# Logic.net
KiCad netlist of a schematic drawn in EAGLE
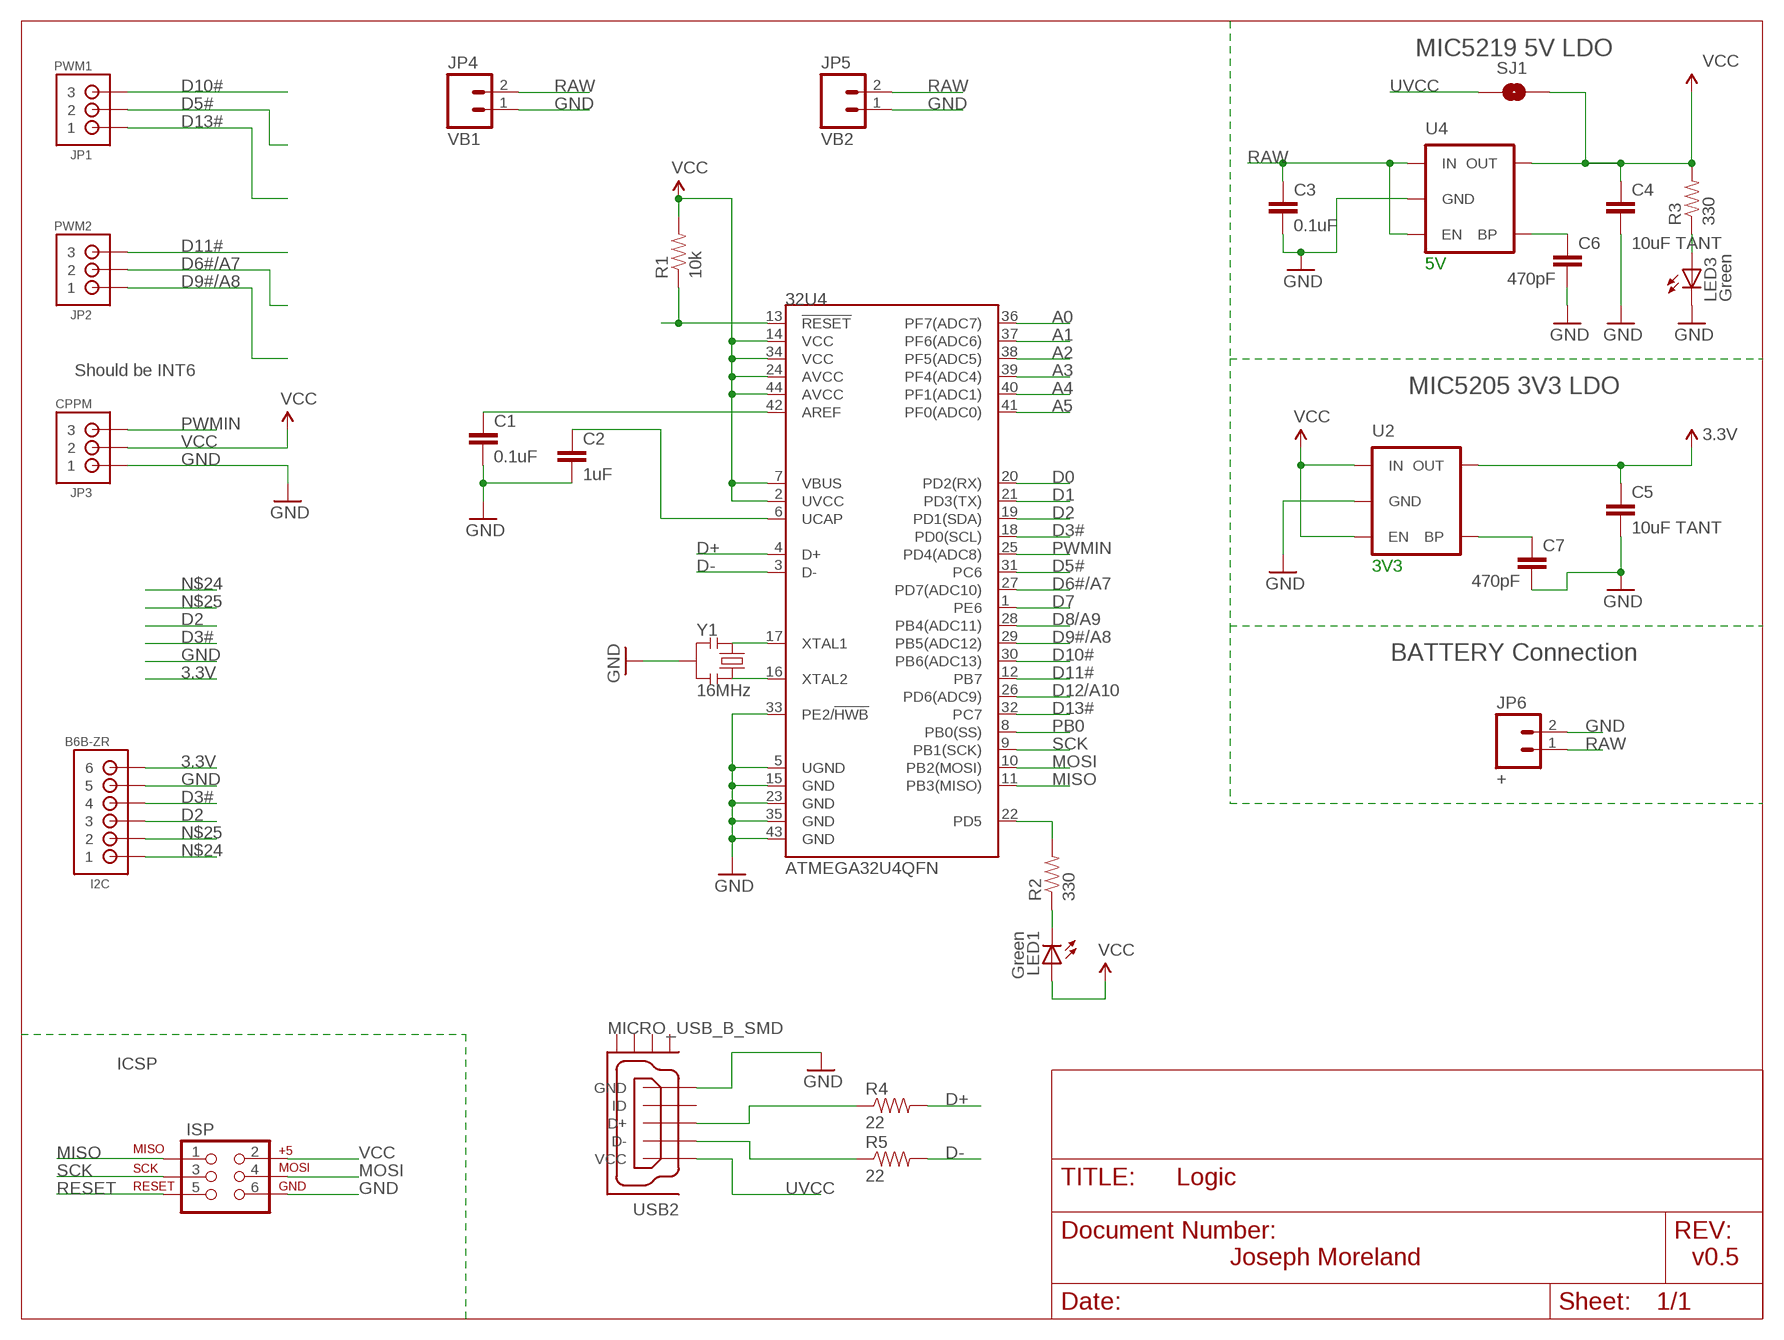
[diagram p0: schematic, sheet 1]

(export (version "E")
  (design (tool "Eeschema 10.0.6"))
  (components
    (comp (ref "32U4")
      (value "ATMEGA32U4QFN")
      (footprint "eagle-import:SPARKFUN-DIGITALIC_QFN-44")
      (fields (field (name "PARTNO") "ATMEGA32U4-MU"))
      (libsource (lib "eagle-import") (part "ATMEGA32U4QFN"))
    )
    (comp (ref "C1")
      (value "0.1uF")
      (footprint "eagle-import:0603-CAP")
      (fields (field (name "PARTNO") "C0603C104K8RACTU"))
      (libsource (lib "eagle-import") (part "CAP0603-CAP"))
    )
    (comp (ref "C2")
      (value "1uF")
      (footprint "eagle-import:0402-CAP")
      (fields (field (name "PARTNO") "LMK105BJ105KV-F"))
      (libsource (lib "eagle-import") (part "CAP0402-CAP"))
    )
    (comp (ref "C3")
      (value "0.1uF")
      (footprint "eagle-import:0603-CAP")
      (fields (field (name "PARTNO") "C0603C104K8RACTU"))
      (libsource (lib "eagle-import") (part "CAP0603-CAP"))
    )
    (comp (ref "C4")
      (value "10uF TANT")
      (footprint "eagle-import:0603-CAP")
      (fields (field (name "PARTNO") "TCM1A106M8R"))
      (libsource (lib "eagle-import") (part "CAP0603-CAP"))
    )
    (comp (ref "C5")
      (value "10uF TANT")
      (footprint "eagle-import:0603-CAP")
      (fields (field (name "PARTNO") "TCM1A106M8R"))
      (libsource (lib "eagle-import") (part "CAP0603-CAP"))
    )
    (comp (ref "C6")
      (value "470pF")
      (footprint "eagle-import:0603-CAP")
      (fields (field (name "PARTNO") "C0603C471K5RACTU"))
      (libsource (lib "eagle-import") (part "CAP0603-CAP"))
    )
    (comp (ref "C7")
      (value "470pF")
      (footprint "eagle-import:0603-CAP")
      (fields (field (name "PARTNO") "C0603C471K5RACTU"))
      (libsource (lib "eagle-import") (part "CAP0603-CAP"))
    )
    (comp (ref "I2C")
      (value "B6B-ZR")
      (footprint "eagle-import:B6B-ZR")
      (libsource (lib "eagle-import") (part "B6B-ZR"))
    )
    (comp (ref "ISP")
      (value "ICSP")
      (footprint "eagle-import:2X3_LOCK")
      (libsource (lib "eagle-import") (part "AVR_SPI_PRG_62X3_LOCK"))
    )
    (comp (ref "JP1")
      (value "PWM1")
      (footprint "eagle-import:B3B-ZR")
      (fields (field (name "PARTNO") "M20-9990346"))
      (libsource (lib "eagle-import") (part "B3B-ZR"))
    )
    (comp (ref "JP2")
      (value "PWM2")
      (footprint "eagle-import:B3B-ZR")
      (fields (field (name "PARTNO") "M20-9990346"))
      (libsource (lib "eagle-import") (part "B3B-ZR"))
    )
    (comp (ref "JP3")
      (value "CPPM")
      (footprint "eagle-import:B3B-ZR")
      (fields (field (name "PARTNO") "M20-9990346"))
      (libsource (lib "eagle-import") (part "B3B-ZR"))
    )
    (comp (ref "JP4")
      (value "VB1")
      (footprint "eagle-import:1X02_LOCK")
      (fields (field (name "PARTNO") "22-28-4025"))
      (libsource (lib "eagle-import") (part "M02LOCK"))
    )
    (comp (ref "JP5")
      (value "VB2")
      (footprint "eagle-import:1X02_LOCK")
      (fields (field (name "PARTNO") "22-28-4025"))
      (libsource (lib "eagle-import") (part "M02LOCK"))
    )
    (comp (ref "JP6")
      (value "+")
      (footprint "eagle-import:1X02_LOCK")
      (fields (field (name "PARTNO") "22-28-4025"))
      (libsource (lib "eagle-import") (part "M02LOCK"))
    )
    (comp (ref "LED1")
      (value "Green")
      (footprint "eagle-import:LED-0603")
      (fields (field (name "PARTNO") "LTST-C190KGKT"))
      (libsource (lib "eagle-import") (part "LED0603"))
    )
    (comp (ref "LED3")
      (value "Green")
      (footprint "eagle-import:LED-0603")
      (fields (field (name "PARTNO") "LTST-C190KGKT"))
      (libsource (lib "eagle-import") (part "LED0603"))
    )
    (comp (ref "R1")
      (value "10k")
      (footprint "eagle-import:0402-RES")
      (fields (field (name "PARTNO") "CRCW040210K0FKED"))
      (libsource (lib "eagle-import") (part "RESISTOR0402-RES"))
    )
    (comp (ref "R2")
      (value "330")
      (footprint "eagle-import:0402-RES")
      (fields (field (name "PARTNO") "CRCW0402330RJNED"))
      (libsource (lib "eagle-import") (part "RESISTOR0402-RES"))
    )
    (comp (ref "R3")
      (value "330")
      (footprint "eagle-import:0402-RES")
      (fields (field (name "PARTNO") "CRCW0402330RJNED"))
      (libsource (lib "eagle-import") (part "RESISTOR0402-RES"))
    )
    (comp (ref "R4")
      (value "22")
      (footprint "eagle-import:0402-RES")
      (fields (field (name "PARTNO") "CRCW040222R0JNED"))
      (libsource (lib "eagle-import") (part "RESISTOR0402-RES"))
    )
    (comp (ref "R5")
      (value "22")
      (footprint "eagle-import:0402-RES")
      (fields (field (name "PARTNO") "CRCW040222R0JNED"))
      (libsource (lib "eagle-import") (part "RESISTOR0402-RES"))
    )
    (comp (ref "SJ1")
      (value "SOLDERJUMPERNO")
      (footprint "eagle-import:SJ_2S-NO")
      (fields (field (name "PARTNO") "DNP"))
      (libsource (lib "eagle-import") (part "SOLDERJUMPERNO"))
    )
    (comp (ref "U2")
      (value "MIC52053v3")
      (footprint "eagle-import:SOT23-5")
      (fields (field (name "PARTNO") "MIC5205-3.3YM5 TR"))
      (libsource (lib "eagle-import") (part "V_REG_LDOSMD"))
    )
    (comp (ref "U4")
      (value "MIC5219 5V")
      (footprint "eagle-import:SOT23-5")
      (fields (field (name "PARTNO") "MIC5219-5.0YM5 TR"))
      (libsource (lib "eagle-import") (part "V_REG_MIC52195V"))
    )
    (comp (ref "USB2")
      (value "MICRO_USB_B_SMD")
      (footprint "eagle-import:MOLEX_MICRO_USB_B_BOTTOM_MOUNT")
      (fields (field (name "PARTNO") "473460001"))
      (libsource (lib "eagle-import") (part "MICRO_USB_B_SMD"))
    )
    (comp (ref "Y1")
      (value "16MHz")
      (footprint "eagle-import:RESONATOR-SMD")
      (fields (field (name "PARTNO") "CSTCE16M0V53-R0"))
      (libsource (lib "eagle-import") (part "RESONATOR16MHZ"))
    )
  )
  (nets
    (net (code "1") (name "/A0") (class "Default")
      (node (ref "32U4") (pin "36") (pinfunction "PF7(ADC7)_36") (pintype "bidirectional"))
    )
    (net (code "2") (name "/A1") (class "Default")
      (node (ref "32U4") (pin "37") (pinfunction "PF6(ADC6)_37") (pintype "bidirectional"))
    )
    (net (code "3") (name "/A2") (class "Default")
      (node (ref "32U4") (pin "38") (pinfunction "PF5(ADC5)_38") (pintype "bidirectional"))
    )
    (net (code "4") (name "/A3") (class "Default")
      (node (ref "32U4") (pin "39") (pinfunction "PF4(ADC4)_39") (pintype "bidirectional"))
    )
    (net (code "5") (name "/A4") (class "Default")
      (node (ref "32U4") (pin "40") (pinfunction "PF1(ADC1)_40") (pintype "bidirectional"))
    )
    (net (code "6") (name "/A5") (class "Default")
      (node (ref "32U4") (pin "41") (pinfunction "PF0(ADC0)_41") (pintype "bidirectional"))
    )
    (net (code "7") (name "/D+") (class "Default")
      (node (ref "32U4") (pin "4") (pinfunction "D+_4") (pintype "bidirectional"))
      (node (ref "R4") (pin "2") (pinfunction "2_2") (pintype "passive"))
    )
    (net (code "8") (name "/D-") (class "Default")
      (node (ref "32U4") (pin "3") (pinfunction "D-_3") (pintype "bidirectional"))
      (node (ref "R5") (pin "2") (pinfunction "2_2") (pintype "passive"))
    )
    (net (code "9") (name "/D0") (class "Default")
      (node (ref "32U4") (pin "20") (pinfunction "PD2(RX)_20") (pintype "bidirectional"))
    )
    (net (code "10") (name "/D1") (class "Default")
      (node (ref "32U4") (pin "21") (pinfunction "PD3(TX)_21") (pintype "bidirectional"))
    )
    (net (code "11") (name "/D2") (class "Default")
      (node (ref "32U4") (pin "19") (pinfunction "PD1(SDA)_19") (pintype "bidirectional"))
      (node (ref "I2C") (pin "3") (pinfunction "3_3") (pintype "bidirectional"))
    )
    (net (code "12") (name "/D3#") (class "Default")
      (node (ref "32U4") (pin "18") (pinfunction "PD0(SCL)_18") (pintype "bidirectional"))
      (node (ref "I2C") (pin "4") (pinfunction "4_4") (pintype "bidirectional"))
    )
    (net (code "13") (name "/D5#") (class "Default")
      (node (ref "32U4") (pin "31") (pinfunction "PC6_31") (pintype "bidirectional"))
      (node (ref "JP1") (pin "2") (pinfunction "2_2") (pintype "bidirectional"))
    )
    (net (code "14") (name "/D6#{slash}A7") (class "Default")
      (node (ref "32U4") (pin "27") (pinfunction "PD7(ADC10)_27") (pintype "bidirectional"))
      (node (ref "JP2") (pin "2") (pinfunction "2_2") (pintype "bidirectional"))
    )
    (net (code "15") (name "/D7") (class "Default")
      (node (ref "32U4") (pin "1") (pinfunction "PE6_1") (pintype "bidirectional"))
    )
    (net (code "16") (name "/D8{slash}A9") (class "Default")
      (node (ref "32U4") (pin "28") (pinfunction "PB4(ADC11)_28") (pintype "bidirectional"))
    )
    (net (code "17") (name "/D9#{slash}A8") (class "Default")
      (node (ref "32U4") (pin "29") (pinfunction "PB5(ADC12)_29") (pintype "bidirectional"))
      (node (ref "JP2") (pin "1") (pinfunction "1_1") (pintype "bidirectional"))
    )
    (net (code "18") (name "/D10#") (class "Default")
      (node (ref "32U4") (pin "30") (pinfunction "PB6(ADC13)_30") (pintype "bidirectional"))
      (node (ref "JP1") (pin "3") (pinfunction "3_3") (pintype "bidirectional"))
    )
    (net (code "19") (name "/D11#") (class "Default")
      (node (ref "32U4") (pin "12") (pinfunction "PB7_12") (pintype "bidirectional"))
      (node (ref "JP2") (pin "3") (pinfunction "3_3") (pintype "bidirectional"))
    )
    (net (code "20") (name "/D12{slash}A10") (class "Default")
      (node (ref "32U4") (pin "26") (pinfunction "PD6(ADC9)_26") (pintype "bidirectional"))
    )
    (net (code "21") (name "/D13#") (class "Default")
      (node (ref "32U4") (pin "32") (pinfunction "PC7_32") (pintype "bidirectional"))
      (node (ref "JP1") (pin "1") (pinfunction "1_1") (pintype "bidirectional"))
    )
    (net (code "22") (name "/MISO") (class "Default")
      (node (ref "32U4") (pin "11") (pinfunction "PB3(MISO)_11") (pintype "bidirectional"))
      (node (ref "ISP") (pin "1") (pinfunction "1_1") (pintype "passive"))
    )
    (net (code "23") (name "/MOSI") (class "Default")
      (node (ref "32U4") (pin "10") (pinfunction "PB2(MOSI)_10") (pintype "bidirectional"))
      (node (ref "ISP") (pin "4") (pinfunction "4_4") (pintype "passive"))
    )
    (net (code "24") (name "/N$24") (class "Default")
      (node (ref "I2C") (pin "1") (pinfunction "1_1") (pintype "bidirectional"))
    )
    (net (code "25") (name "/N$25") (class "Default")
      (node (ref "I2C") (pin "2") (pinfunction "2_2") (pintype "bidirectional"))
    )
    (net (code "26") (name "/PB0") (class "Default")
      (node (ref "32U4") (pin "8") (pinfunction "PB0(SS)_8") (pintype "bidirectional"))
    )
    (net (code "27") (name "/PWMIN") (class "Default")
      (node (ref "32U4") (pin "25") (pinfunction "PD4(ADC8)_25") (pintype "bidirectional"))
      (node (ref "JP3") (pin "3") (pinfunction "3_3") (pintype "bidirectional"))
    )
    (net (code "28") (name "/RAW") (class "Default")
      (node (ref "C3") (pin "1") (pinfunction "1_1") (pintype "passive"))
      (node (ref "JP4") (pin "2") (pinfunction "2_2") (pintype "passive"))
      (node (ref "JP5") (pin "2") (pinfunction "2_2") (pintype "passive"))
      (node (ref "JP6") (pin "1") (pinfunction "1_1") (pintype "passive"))
      (node (ref "U4") (pin "1") (pinfunction "IN_1") (pintype "input"))
      (node (ref "U4") (pin "3") (pinfunction "EN_3") (pintype "input"))
    )
    (net (code "29") (name "/RESET") (class "Default")
      (node (ref "32U4") (pin "13") (pinfunction "~{RESET}_13") (pintype "bidirectional"))
      (node (ref "ISP") (pin "5") (pinfunction "5_5") (pintype "passive"))
      (node (ref "R1") (pin "1") (pinfunction "1_1") (pintype "passive"))
    )
    (net (code "30") (name "/SCK") (class "Default")
      (node (ref "32U4") (pin "9") (pinfunction "PB1(SCK)_9") (pintype "bidirectional"))
      (node (ref "ISP") (pin "3") (pinfunction "3_3") (pintype "passive"))
    )
    (net (code "31") (name "/UVCC") (class "Default")
      (node (ref "SJ1") (pin "1") (pinfunction "1_1") (pintype "passive"))
      (node (ref "USB2") (pin "1") (pinfunction "VCC_1") (pintype "input"))
    )
    (net (code "32") (name "3.3V") (class "Default")
      (node (ref "C5") (pin "1") (pinfunction "1_1") (pintype "passive"))
      (node (ref "I2C") (pin "6") (pinfunction "6_6") (pintype "bidirectional"))
      (node (ref "U2") (pin "5") (pinfunction "OUT_5") (pintype "passive"))
    )
    (net (code "33") (name "GND") (class "Default")
      (node (ref "32U4") (pin "15") (pinfunction "GND_15") (pintype "bidirectional"))
      (node (ref "32U4") (pin "23") (pinfunction "GND_23") (pintype "bidirectional"))
      (node (ref "32U4") (pin "33") (pinfunction "PE2/~{HWB}_33") (pintype "bidirectional"))
      (node (ref "32U4") (pin "35") (pinfunction "GND_35") (pintype "bidirectional"))
      (node (ref "32U4") (pin "43") (pinfunction "GND_43") (pintype "bidirectional"))
      (node (ref "32U4") (pin "5") (pinfunction "UGND_5") (pintype "bidirectional"))
      (node (ref "C1") (pin "2") (pinfunction "2_2") (pintype "passive"))
      (node (ref "C2") (pin "2") (pinfunction "2_2") (pintype "passive"))
      (node (ref "C3") (pin "2") (pinfunction "2_2") (pintype "passive"))
      (node (ref "C4") (pin "2") (pinfunction "2_2") (pintype "passive"))
      (node (ref "C5") (pin "2") (pinfunction "2_2") (pintype "passive"))
      (node (ref "C6") (pin "2") (pinfunction "2_2") (pintype "passive"))
      (node (ref "C7") (pin "2") (pinfunction "2_2") (pintype "passive"))
      (node (ref "I2C") (pin "5") (pinfunction "5_5") (pintype "bidirectional"))
      (node (ref "ISP") (pin "6") (pinfunction "6_6") (pintype "passive"))
      (node (ref "JP3") (pin "1") (pinfunction "1_1") (pintype "bidirectional"))
      (node (ref "JP4") (pin "1") (pinfunction "1_1") (pintype "passive"))
      (node (ref "JP5") (pin "1") (pinfunction "1_1") (pintype "passive"))
      (node (ref "JP6") (pin "2") (pinfunction "2_2") (pintype "passive"))
      (node (ref "LED3") (pin "C") (pinfunction "C_C") (pintype "passive"))
      (node (ref "U2") (pin "2") (pinfunction "GND_2") (pintype "input"))
      (node (ref "U4") (pin "2") (pinfunction "GND_2") (pintype "input"))
      (node (ref "USB2") (pin "5") (pinfunction "GND_5") (pintype "input"))
      (node (ref "Y1") (pin "2") (pinfunction "2_2") (pintype "passive"))
    )
    (net (code "34") (name "Net-(32U4-AREF)") (class "Default")
      (node (ref "32U4") (pin "42") (pinfunction "AREF_42") (pintype "bidirectional"))
      (node (ref "C1") (pin "1") (pinfunction "1_1") (pintype "passive"))
    )
    (net (code "35") (name "Net-(32U4-PD5)") (class "Default")
      (node (ref "32U4") (pin "22") (pinfunction "PD5_22") (pintype "bidirectional"))
      (node (ref "R2") (pin "2") (pinfunction "2_2") (pintype "passive"))
    )
    (net (code "36") (name "Net-(32U4-UCAP)") (class "Default")
      (node (ref "32U4") (pin "6") (pinfunction "UCAP_6") (pintype "bidirectional"))
      (node (ref "C2") (pin "1") (pinfunction "1_1") (pintype "passive"))
    )
    (net (code "37") (name "Net-(32U4-XTAL1)") (class "Default")
      (node (ref "32U4") (pin "17") (pinfunction "XTAL1_17") (pintype "bidirectional"))
      (node (ref "Y1") (pin "1") (pinfunction "1_1") (pintype "passive"))
    )
    (net (code "38") (name "Net-(32U4-XTAL2)") (class "Default")
      (node (ref "32U4") (pin "16") (pinfunction "XTAL2_16") (pintype "bidirectional"))
      (node (ref "Y1") (pin "3") (pinfunction "3_3") (pintype "passive"))
    )
    (net (code "39") (name "Net-(LED1-PadC)") (class "Default")
      (node (ref "LED1") (pin "C") (pinfunction "C_C") (pintype "passive"))
      (node (ref "R2") (pin "1") (pinfunction "1_1") (pintype "passive"))
    )
    (net (code "40") (name "Net-(LED3-PadA)") (class "Default")
      (node (ref "LED3") (pin "A") (pinfunction "A_A") (pintype "passive"))
      (node (ref "R3") (pin "1") (pinfunction "1_1") (pintype "passive"))
    )
    (net (code "41") (name "Net-(U2-BP)") (class "Default")
      (node (ref "C7") (pin "1") (pinfunction "1_1") (pintype "passive"))
      (node (ref "U2") (pin "4") (pinfunction "BP_4") (pintype "input"))
    )
    (net (code "42") (name "Net-(U4-BP)") (class "Default")
      (node (ref "C6") (pin "1") (pinfunction "1_1") (pintype "passive"))
      (node (ref "U4") (pin "4") (pinfunction "BP_4") (pintype "input"))
    )
    (net (code "43") (name "Net-(USB2-D+)") (class "Default")
      (node (ref "R4") (pin "1") (pinfunction "1_1") (pintype "passive"))
      (node (ref "USB2") (pin "3") (pinfunction "D+_3") (pintype "input"))
    )
    (net (code "44") (name "Net-(USB2-D-)") (class "Default")
      (node (ref "R5") (pin "1") (pinfunction "1_1") (pintype "passive"))
      (node (ref "USB2") (pin "2") (pinfunction "D-_2") (pintype "input"))
    )
    (net (code "45") (name "VCC") (class "Default")
      (node (ref "32U4") (pin "14") (pinfunction "VCC_14") (pintype "bidirectional"))
      (node (ref "32U4") (pin "2") (pinfunction "UVCC_2") (pintype "bidirectional"))
      (node (ref "32U4") (pin "24") (pinfunction "AVCC_24") (pintype "bidirectional"))
      (node (ref "32U4") (pin "34") (pinfunction "VCC_34") (pintype "bidirectional"))
      (node (ref "32U4") (pin "44") (pinfunction "AVCC_44") (pintype "bidirectional"))
      (node (ref "32U4") (pin "7") (pinfunction "VBUS_7") (pintype "bidirectional"))
      (node (ref "C4") (pin "1") (pinfunction "1_1") (pintype "passive"))
      (node (ref "ISP") (pin "2") (pinfunction "2_2") (pintype "passive"))
      (node (ref "JP3") (pin "2") (pinfunction "2_2") (pintype "bidirectional"))
      (node (ref "LED1") (pin "A") (pinfunction "A_A") (pintype "passive"))
      (node (ref "R1") (pin "2") (pinfunction "2_2") (pintype "passive"))
      (node (ref "R3") (pin "2") (pinfunction "2_2") (pintype "passive"))
      (node (ref "SJ1") (pin "2") (pinfunction "2_2") (pintype "passive"))
      (node (ref "U2") (pin "1") (pinfunction "IN_1") (pintype "input"))
      (node (ref "U2") (pin "3") (pinfunction "EN_3") (pintype "input"))
      (node (ref "U4") (pin "5") (pinfunction "OUT_5") (pintype "passive"))
    )
    (net (code "46") (name "unconnected-(USB2-ID-Pad4)") (class "Default")
      (node (ref "USB2") (pin "4") (pinfunction "ID_4") (pintype "input"))
    )
    (net (code "47") (name "unconnected-(USB2-PadGND1)") (class "Default")
      (node (ref "USB2") (pin "GND1") (pinfunction "GND1_GND1") (pintype "bidirectional"))
    )
    (net (code "48") (name "unconnected-(USB2-PadGND2)") (class "Default")
      (node (ref "USB2") (pin "GND2") (pinfunction "GND2_GND2") (pintype "bidirectional"))
    )
    (net (code "49") (name "unconnected-(USB2-PadGND3)") (class "Default")
      (node (ref "USB2") (pin "GND3") (pinfunction "GND3_GND3") (pintype "bidirectional"))
    )
    (net (code "50") (name "unconnected-(USB2-PadGND4)") (class "Default")
      (node (ref "USB2") (pin "GND4") (pinfunction "GND4_GND4") (pintype "bidirectional"))
    )
  )
)
